# LifterV03.net
KiCad netlist of a schematic drawn in EAGLE
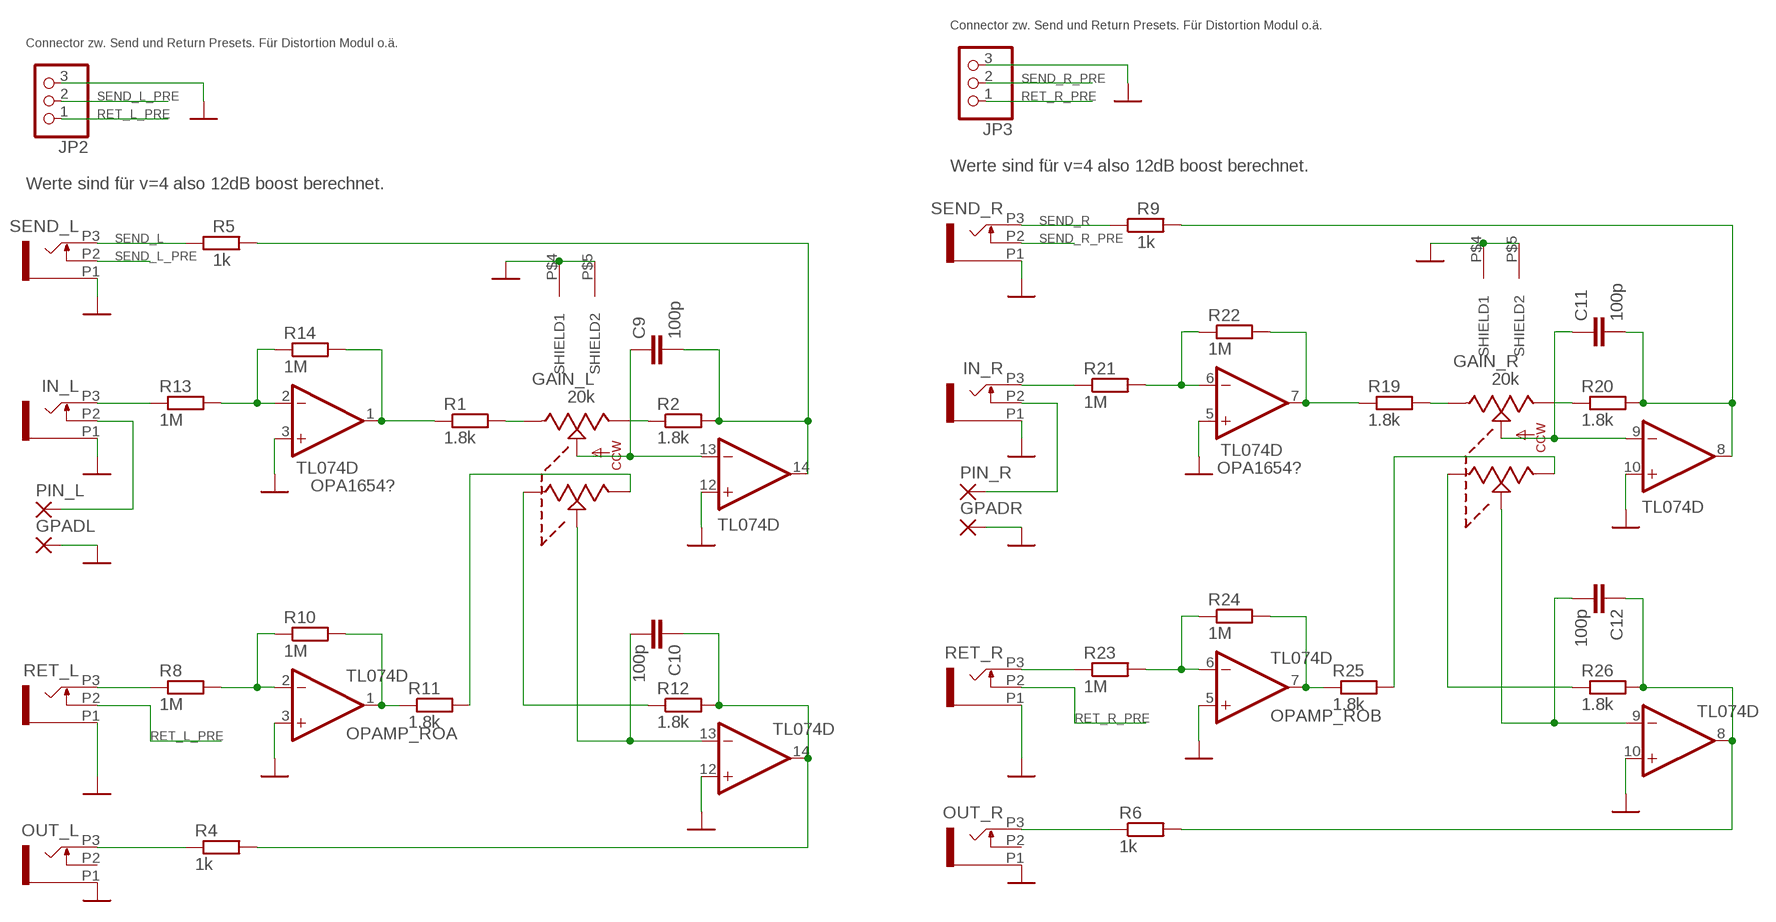
[diagram p0: schematic, sheet 1]
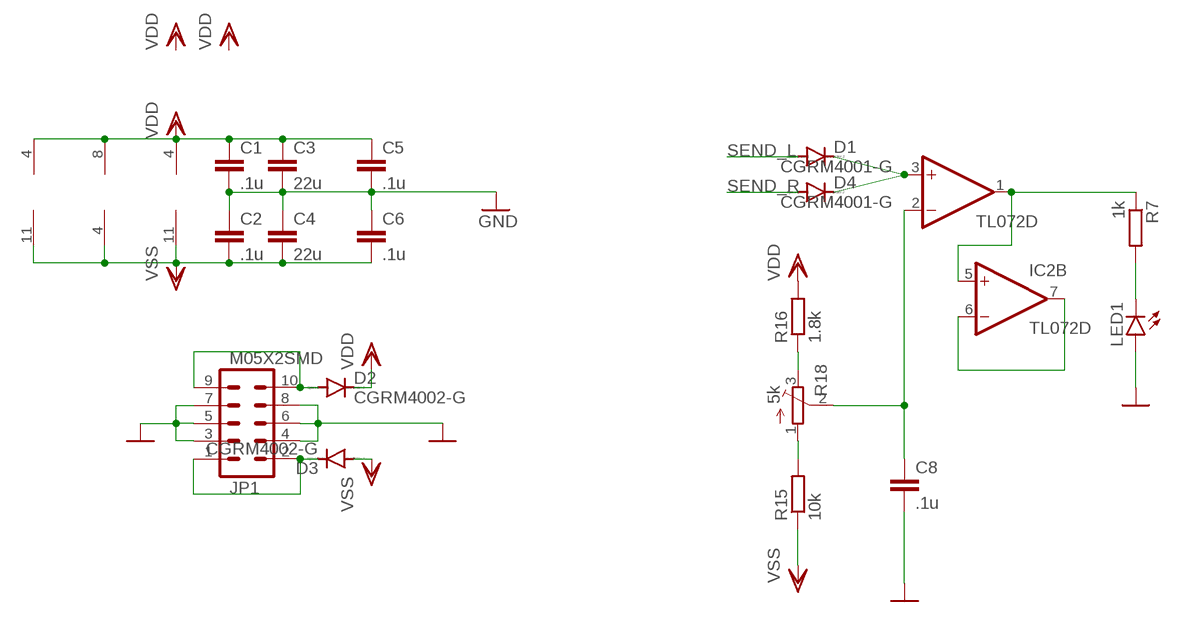
[diagram p1: schematic, sheet 2]

(export (version "E")
  (design (tool "Eeschema 10.0.6"))
  (components
    (comp (ref "C9")
      (value "100p")
      (footprint "eagle-import:C0603")
      (libsource (lib "eagle-import") (part "C-EUC0603"))
    )
    (comp (ref "C10")
      (value "100p")
      (footprint "eagle-import:C0603")
      (libsource (lib "eagle-import") (part "C-EUC0603"))
    )
    (comp (ref "C11")
      (value "100p")
      (footprint "eagle-import:C0603")
      (libsource (lib "eagle-import") (part "C-EUC0603"))
    )
    (comp (ref "C12")
      (value "100p")
      (footprint "eagle-import:C0603")
      (libsource (lib "eagle-import") (part "C-EUC0603"))
    )
    (comp (ref "GAIN_L")
      (value "20k")
      (footprint "eagle-import:TT_2TAP_VERTICAL")
      (libsource (lib "eagle-import") (part "POT_US_2X"))
    )
    (comp (ref "GAIN_R")
      (value "20k")
      (footprint "eagle-import:TT_2TAP_VERTICAL")
      (libsource (lib "eagle-import") (part "POT_US_2X"))
    )
    (comp (ref "GPADL")
      (value "3,17/1,3")
      (footprint "eagle-import:3,17_1,3")
      (libsource (lib "eagle-import") (part "3,17/1,3"))
    )
    (comp (ref "GPADR")
      (value "3,17/1,3")
      (footprint "eagle-import:3,17_1,3")
      (libsource (lib "eagle-import") (part "3,17/1,3"))
    )
    (comp (ref "IN_L")
      (value "PJ301_THONKICONN6")
      (footprint "eagle-import:WQP_PJ_301M6")
      (libsource (lib "eagle-import") (part "PJ301_THONKICONN6"))
    )
    (comp (ref "IN_R")
      (value "PJ301_THONKICONN6")
      (footprint "eagle-import:WQP_PJ_301M6")
      (libsource (lib "eagle-import") (part "PJ301_THONKICONN6"))
    )
    (comp (ref "JP2")
      (value "PINHD-1X3")
      (footprint "eagle-import:1X03")
      (libsource (lib "eagle-import") (part "PINHD-1X3"))
    )
    (comp (ref "JP3")
      (value "PINHD-1X3")
      (footprint "eagle-import:1X03")
      (libsource (lib "eagle-import") (part "PINHD-1X3"))
    )
    (comp (ref "OPAMP_IS")
      (value "TL074D")
      (footprint "eagle-import:SO14")
      (fields (field (name "SPICEPREFIX") "J"))
      (libsource (lib "eagle-import") (part "TL074D"))
    )
    (comp (ref "OPAMP_RO")
      (value "TL074D")
      (footprint "eagle-import:SO14")
      (fields (field (name "SPICEPREFIX") "J"))
      (libsource (lib "eagle-import") (part "TL074D"))
    )
    (comp (ref "OUT_L")
      (value "PJ301_THONKICONN6")
      (footprint "eagle-import:WQP_PJ_301M6")
      (libsource (lib "eagle-import") (part "PJ301_THONKICONN6"))
    )
    (comp (ref "OUT_R")
      (value "PJ301_THONKICONN6")
      (footprint "eagle-import:WQP_PJ_301M6")
      (libsource (lib "eagle-import") (part "PJ301_THONKICONN6"))
    )
    (comp (ref "PIN_L")
      (value "3,17/1,3")
      (footprint "eagle-import:3,17_1,3")
      (libsource (lib "eagle-import") (part "3,17/1,3"))
    )
    (comp (ref "PIN_R")
      (value "3,17/1,3")
      (footprint "eagle-import:3,17_1,3")
      (libsource (lib "eagle-import") (part "3,17/1,3"))
    )
    (comp (ref "R1")
      (value "1.8k")
      (footprint "eagle-import:R0603")
      (libsource (lib "eagle-import") (part "R-EU_R0603"))
    )
    (comp (ref "R2")
      (value "1.8k")
      (footprint "eagle-import:R0603")
      (libsource (lib "eagle-import") (part "R-EU_R0603"))
    )
    (comp (ref "R4")
      (value "1k")
      (footprint "eagle-import:R0603")
      (libsource (lib "eagle-import") (part "R-EU_R0603"))
    )
    (comp (ref "R5")
      (value "1k")
      (footprint "eagle-import:R0603")
      (libsource (lib "eagle-import") (part "R-EU_R0603"))
    )
    (comp (ref "R6")
      (value "1k")
      (footprint "eagle-import:R0603")
      (libsource (lib "eagle-import") (part "R-EU_R0603"))
    )
    (comp (ref "R8")
      (value "1M")
      (footprint "eagle-import:R0603")
      (libsource (lib "eagle-import") (part "R-EU_R0603"))
    )
    (comp (ref "R9")
      (value "1k")
      (footprint "eagle-import:R0603")
      (libsource (lib "eagle-import") (part "R-EU_R0603"))
    )
    (comp (ref "R10")
      (value "1M")
      (footprint "eagle-import:R0603")
      (libsource (lib "eagle-import") (part "R-EU_R0603"))
    )
    (comp (ref "R11")
      (value "1.8k")
      (footprint "eagle-import:R0603")
      (libsource (lib "eagle-import") (part "R-EU_R0603"))
    )
    (comp (ref "R12")
      (value "1.8k")
      (footprint "eagle-import:R0603")
      (libsource (lib "eagle-import") (part "R-EU_R0603"))
    )
    (comp (ref "R13")
      (value "1M")
      (footprint "eagle-import:R0603")
      (libsource (lib "eagle-import") (part "R-EU_R0603"))
    )
    (comp (ref "R14")
      (value "1M")
      (footprint "eagle-import:R0603")
      (libsource (lib "eagle-import") (part "R-EU_R0603"))
    )
    (comp (ref "R19")
      (value "1.8k")
      (footprint "eagle-import:R0603")
      (libsource (lib "eagle-import") (part "R-EU_R0603"))
    )
    (comp (ref "R20")
      (value "1.8k")
      (footprint "eagle-import:R0603")
      (libsource (lib "eagle-import") (part "R-EU_R0603"))
    )
    (comp (ref "R21")
      (value "1M")
      (footprint "eagle-import:R0603")
      (libsource (lib "eagle-import") (part "R-EU_R0603"))
    )
    (comp (ref "R22")
      (value "1M")
      (footprint "eagle-import:R0603")
      (libsource (lib "eagle-import") (part "R-EU_R0603"))
    )
    (comp (ref "R23")
      (value "1M")
      (footprint "eagle-import:R0603")
      (libsource (lib "eagle-import") (part "R-EU_R0603"))
    )
    (comp (ref "R24")
      (value "1M")
      (footprint "eagle-import:R0603")
      (libsource (lib "eagle-import") (part "R-EU_R0603"))
    )
    (comp (ref "R25")
      (value "1.8k")
      (footprint "eagle-import:R0603")
      (libsource (lib "eagle-import") (part "R-EU_R0603"))
    )
    (comp (ref "R26")
      (value "1.8k")
      (footprint "eagle-import:R0603")
      (libsource (lib "eagle-import") (part "R-EU_R0603"))
    )
    (comp (ref "RET_L")
      (value "PJ301_THONKICONN6")
      (footprint "eagle-import:WQP_PJ_301M6")
      (libsource (lib "eagle-import") (part "PJ301_THONKICONN6"))
    )
    (comp (ref "RET_R")
      (value "PJ301_THONKICONN6")
      (footprint "eagle-import:WQP_PJ_301M6")
      (libsource (lib "eagle-import") (part "PJ301_THONKICONN6"))
    )
    (comp (ref "SEND_L")
      (value "PJ301_THONKICONN6")
      (footprint "eagle-import:WQP_PJ_301M6")
      (libsource (lib "eagle-import") (part "PJ301_THONKICONN6"))
    )
    (comp (ref "SEND_R")
      (value "PJ301_THONKICONN6")
      (footprint "eagle-import:WQP_PJ_301M6")
      (libsource (lib "eagle-import") (part "PJ301_THONKICONN6"))
    )
    (comp (ref "C1")
      (value ".1u")
      (footprint "eagle-import:C0603")
      (libsource (lib "eagle-import") (part "C-EUC0603"))
    )
    (comp (ref "C2")
      (value ".1u")
      (footprint "eagle-import:C0603")
      (libsource (lib "eagle-import") (part "C-EUC0603"))
    )
    (comp (ref "C3")
      (value "22u")
      (footprint "eagle-import:C1210")
      (libsource (lib "eagle-import") (part "C-EUC1210"))
    )
    (comp (ref "C4")
      (value "22u")
      (footprint "eagle-import:C1210")
      (libsource (lib "eagle-import") (part "C-EUC1210"))
    )
    (comp (ref "C5")
      (value ".1u")
      (footprint "eagle-import:C0603")
      (libsource (lib "eagle-import") (part "C-EUC0603"))
    )
    (comp (ref "C6")
      (value ".1u")
      (footprint "eagle-import:C0603")
      (libsource (lib "eagle-import") (part "C-EUC0603"))
    )
    (comp (ref "C8")
      (value ".1u")
      (footprint "eagle-import:C0603")
      (libsource (lib "eagle-import") (part "C-EUC0603"))
    )
    (comp (ref "D1")
      (value "CGRM4001-G")
      (footprint "eagle-import:SOD-123_MINI-SMA")
      (libsource (lib "eagle-import") (part "CGRM400-G1"))
    )
    (comp (ref "D2")
      (value "CGRM4002-G")
      (footprint "eagle-import:SOD-123_MINI-SMA")
      (libsource (lib "eagle-import") (part "CGRM400-G2"))
    )
    (comp (ref "D3")
      (value "CGRM4002-G")
      (footprint "eagle-import:SOD-123_MINI-SMA")
      (libsource (lib "eagle-import") (part "CGRM400-G2"))
    )
    (comp (ref "D4")
      (value "CGRM4001-G")
      (footprint "eagle-import:SOD-123_MINI-SMA")
      (libsource (lib "eagle-import") (part "CGRM400-G1"))
    )
    (comp (ref "IC2")
      (value "TL072D")
      (footprint "eagle-import:SO08")
      (libsource (lib "eagle-import") (part "TL072D"))
    )
    (comp (ref "JP1")
      (value "M05X2SMD")
      (footprint "eagle-import:2X5-SMD")
      (libsource (lib "eagle-import") (part "M05X2SMD"))
    )
    (comp (ref "LED1")
      (value "LED3MM")
      (footprint "eagle-import:LED3MM")
      (libsource (lib "eagle-import") (part "LED3MM"))
    )
    (comp (ref "R7")
      (value "1k")
      (footprint "eagle-import:R0603")
      (libsource (lib "eagle-import") (part "R-EU_R0603"))
    )
    (comp (ref "R15")
      (value "10k")
      (footprint "eagle-import:R0603")
      (libsource (lib "eagle-import") (part "R-EU_R0603"))
    )
    (comp (ref "R16")
      (value "1.8k")
      (footprint "eagle-import:R0603")
      (libsource (lib "eagle-import") (part "R-EU_R0603"))
    )
    (comp (ref "R18")
      (value "5k")
      (footprint "eagle-import:3223G")
      (libsource (lib "eagle-import") (part "TRIM_EU-3223G"))
    )
  )
  (nets
    (net (code "1") (name "GND") (class "Default")
      (node (ref "C1") (pin "2") (pinfunction "2_2") (pintype "passive"))
      (node (ref "C2") (pin "1") (pinfunction "1_1") (pintype "passive"))
      (node (ref "C3") (pin "2") (pinfunction "2_2") (pintype "passive"))
      (node (ref "C4") (pin "1") (pinfunction "1_1") (pintype "passive"))
      (node (ref "C5") (pin "2") (pinfunction "2_2") (pintype "passive"))
      (node (ref "C6") (pin "1") (pinfunction "1_1") (pintype "passive"))
      (node (ref "C8") (pin "2") (pinfunction "2_2") (pintype "passive"))
      (node (ref "GAIN_L") (pin "P$4") (pinfunction "SHIELD1_P$4") (pintype "bidirectional"))
      (node (ref "GAIN_L") (pin "P$5") (pinfunction "SHIELD2_P$5") (pintype "bidirectional"))
      (node (ref "GAIN_R") (pin "P$4") (pinfunction "SHIELD1_P$4") (pintype "bidirectional"))
      (node (ref "GAIN_R") (pin "P$5") (pinfunction "SHIELD2_P$5") (pintype "bidirectional"))
      (node (ref "GPADL") (pin "1") (pinfunction "P_1") (pintype "passive"))
      (node (ref "GPADR") (pin "1") (pinfunction "P_1") (pintype "passive"))
      (node (ref "IN_L") (pin "P1") (pinfunction "1_P1") (pintype "passive"))
      (node (ref "IN_R") (pin "P1") (pinfunction "1_P1") (pintype "passive"))
      (node (ref "JP1") (pin "3") (pinfunction "3_3") (pintype "passive"))
      (node (ref "JP1") (pin "4") (pinfunction "4_4") (pintype "passive"))
      (node (ref "JP1") (pin "5") (pinfunction "5_5") (pintype "passive"))
      (node (ref "JP1") (pin "6") (pinfunction "6_6") (pintype "passive"))
      (node (ref "JP1") (pin "7") (pinfunction "7_7") (pintype "passive"))
      (node (ref "JP1") (pin "8") (pinfunction "8_8") (pintype "passive"))
      (node (ref "JP2") (pin "3") (pinfunction "3_3") (pintype "passive"))
      (node (ref "JP3") (pin "3") (pinfunction "3_3") (pintype "passive"))
      (node (ref "LED1") (pin "A") (pinfunction "A_A") (pintype "passive"))
      (node (ref "OPAMP_IS") (pin "10") (pinfunction "+IN_10") (pintype "input"))
      (node (ref "OPAMP_IS") (pin "12") (pinfunction "+IN_12") (pintype "input"))
      (node (ref "OPAMP_IS") (pin "3") (pinfunction "+IN_3") (pintype "input"))
      (node (ref "OPAMP_IS") (pin "5") (pinfunction "+IN_5") (pintype "input"))
      (node (ref "OPAMP_RO") (pin "10") (pinfunction "+IN_10") (pintype "input"))
      (node (ref "OPAMP_RO") (pin "12") (pinfunction "+IN_12") (pintype "input"))
      (node (ref "OPAMP_RO") (pin "3") (pinfunction "+IN_3") (pintype "input"))
      (node (ref "OPAMP_RO") (pin "5") (pinfunction "+IN_5") (pintype "input"))
      (node (ref "OUT_L") (pin "P1") (pinfunction "1_P1") (pintype "passive"))
      (node (ref "OUT_R") (pin "P1") (pinfunction "1_P1") (pintype "passive"))
      (node (ref "RET_L") (pin "P1") (pinfunction "1_P1") (pintype "passive"))
      (node (ref "RET_R") (pin "P1") (pinfunction "1_P1") (pintype "passive"))
      (node (ref "SEND_L") (pin "P1") (pinfunction "1_P1") (pintype "passive"))
      (node (ref "SEND_R") (pin "P1") (pinfunction "1_P1") (pintype "passive"))
    )
    (net (code "2") (name "Net-(D2-PadA)") (class "Default")
      (node (ref "D2") (pin "A") (pinfunction "A_A") (pintype "passive"))
      (node (ref "JP1") (pin "10") (pinfunction "10_10") (pintype "passive"))
      (node (ref "JP1") (pin "9") (pinfunction "9_9") (pintype "passive"))
    )
    (net (code "3") (name "Net-(D3-PadC)") (class "Default")
      (node (ref "D3") (pin "C") (pinfunction "C_C") (pintype "passive"))
      (node (ref "JP1") (pin "1") (pinfunction "1_1") (pintype "passive"))
      (node (ref "JP1") (pin "2") (pinfunction "2_2") (pintype "passive"))
    )
    (net (code "4") (name "Net-(GAIN_L-PadCCW)") (class "Default")
      (node (ref "GAIN_L") (pin "CCW") (pinfunction "CCW_CCW") (pintype "passive"))
      (node (ref "R2") (pin "1") (pinfunction "1_1") (pintype "passive"))
    )
    (net (code "5") (name "Net-(GAIN_L-PadCCW1)") (class "Default")
      (node (ref "GAIN_L") (pin "CCW1") (pinfunction "CCW1_CCW1") (pintype "passive"))
      (node (ref "R11") (pin "2") (pinfunction "2_2") (pintype "passive"))
    )
    (net (code "6") (name "Net-(GAIN_L-PadCW)") (class "Default")
      (node (ref "GAIN_L") (pin "CW") (pinfunction "CW_CW") (pintype "passive"))
      (node (ref "R1") (pin "2") (pinfunction "2_2") (pintype "passive"))
    )
    (net (code "7") (name "Net-(GAIN_L-PadCW1)") (class "Default")
      (node (ref "GAIN_L") (pin "CW1") (pinfunction "CW1_CW1") (pintype "passive"))
      (node (ref "R12") (pin "1") (pinfunction "1_1") (pintype "passive"))
    )
    (net (code "8") (name "Net-(GAIN_R-PadCCW)") (class "Default")
      (node (ref "GAIN_R") (pin "CCW") (pinfunction "CCW_CCW") (pintype "passive"))
      (node (ref "R20") (pin "1") (pinfunction "1_1") (pintype "passive"))
    )
    (net (code "9") (name "Net-(GAIN_R-PadCCW1)") (class "Default")
      (node (ref "GAIN_R") (pin "CCW1") (pinfunction "CCW1_CCW1") (pintype "passive"))
      (node (ref "R25") (pin "2") (pinfunction "2_2") (pintype "passive"))
    )
    (net (code "10") (name "Net-(GAIN_R-PadCW)") (class "Default")
      (node (ref "GAIN_R") (pin "CW") (pinfunction "CW_CW") (pintype "passive"))
      (node (ref "R19") (pin "2") (pinfunction "2_2") (pintype "passive"))
    )
    (net (code "11") (name "Net-(GAIN_R-PadCW1)") (class "Default")
      (node (ref "GAIN_R") (pin "CW1") (pinfunction "CW1_CW1") (pintype "passive"))
      (node (ref "R26") (pin "1") (pinfunction "1_1") (pintype "passive"))
    )
    (net (code "12") (name "Net-(IC2A-+IN)") (class "Default")
      (node (ref "D1") (pin "C") (pinfunction "C_C") (pintype "passive"))
      (node (ref "D4") (pin "C") (pinfunction "C_C") (pintype "passive"))
      (node (ref "IC2") (pin "3") (pinfunction "+IN_3") (pintype "input"))
    )
    (net (code "13") (name "Net-(IC2A--IN)") (class "Default")
      (node (ref "C8") (pin "1") (pinfunction "1_1") (pintype "passive"))
      (node (ref "IC2") (pin "2") (pinfunction "-IN_2") (pintype "input"))
      (node (ref "R18") (pin "2") (pinfunction "S_2") (pintype "passive"))
    )
    (net (code "14") (name "Net-(IC2A-OUT)") (class "Default")
      (node (ref "IC2") (pin "1") (pinfunction "OUT_1") (pintype "output"))
      (node (ref "IC2") (pin "5") (pinfunction "+IN_5") (pintype "input"))
      (node (ref "R7") (pin "1") (pinfunction "1_1") (pintype "passive"))
    )
    (net (code "15") (name "Net-(IC2B--IN)") (class "Default")
      (node (ref "IC2") (pin "6") (pinfunction "-IN_6") (pintype "input"))
      (node (ref "IC2") (pin "7") (pinfunction "OUT_7") (pintype "output"))
    )
    (net (code "16") (name "Net-(IN_L-2)") (class "Default")
      (node (ref "IN_L") (pin "P2") (pinfunction "2_P2") (pintype "passive"))
      (node (ref "PIN_L") (pin "1") (pinfunction "P_1") (pintype "passive"))
    )
    (net (code "17") (name "Net-(IN_L-3)") (class "Default")
      (node (ref "IN_L") (pin "P3") (pinfunction "3_P3") (pintype "passive"))
      (node (ref "R13") (pin "1") (pinfunction "1_1") (pintype "passive"))
    )
    (net (code "18") (name "Net-(IN_R-2)") (class "Default")
      (node (ref "IN_R") (pin "P2") (pinfunction "2_P2") (pintype "passive"))
      (node (ref "PIN_R") (pin "1") (pinfunction "P_1") (pintype "passive"))
    )
    (net (code "19") (name "Net-(IN_R-3)") (class "Default")
      (node (ref "IN_R") (pin "P3") (pinfunction "3_P3") (pintype "passive"))
      (node (ref "R21") (pin "1") (pinfunction "1_1") (pintype "passive"))
    )
    (net (code "20") (name "Net-(LED1-C)") (class "Default")
      (node (ref "LED1") (pin "K") (pinfunction "C_K") (pintype "passive"))
      (node (ref "R7") (pin "2") (pinfunction "2_2") (pintype "passive"))
    )
    (net (code "21") (name "Net-(OPAMP_ISA--IN)") (class "Default")
      (node (ref "OPAMP_IS") (pin "2") (pinfunction "-IN_2") (pintype "input"))
      (node (ref "R13") (pin "2") (pinfunction "2_2") (pintype "passive"))
      (node (ref "R14") (pin "1") (pinfunction "1_1") (pintype "passive"))
    )
    (net (code "22") (name "Net-(OPAMP_ISA-OUT)") (class "Default")
      (node (ref "OPAMP_IS") (pin "1") (pinfunction "OUT_1") (pintype "output"))
      (node (ref "R1") (pin "1") (pinfunction "1_1") (pintype "passive"))
      (node (ref "R14") (pin "2") (pinfunction "2_2") (pintype "passive"))
    )
    (net (code "23") (name "Net-(OPAMP_ISB--IN)") (class "Default")
      (node (ref "OPAMP_IS") (pin "6") (pinfunction "-IN_6") (pintype "input"))
      (node (ref "R21") (pin "2") (pinfunction "2_2") (pintype "passive"))
      (node (ref "R22") (pin "1") (pinfunction "1_1") (pintype "passive"))
    )
    (net (code "24") (name "Net-(OPAMP_ISB-OUT)") (class "Default")
      (node (ref "OPAMP_IS") (pin "7") (pinfunction "OUT_7") (pintype "output"))
      (node (ref "R19") (pin "1") (pinfunction "1_1") (pintype "passive"))
      (node (ref "R22") (pin "2") (pinfunction "2_2") (pintype "passive"))
    )
    (net (code "25") (name "Net-(OPAMP_ISC--IN)") (class "Default")
      (node (ref "C11") (pin "1") (pinfunction "1_1") (pintype "passive"))
      (node (ref "GAIN_R") (pin "CENTER") (pinfunction "CENTER_CENTER") (pintype "passive"))
      (node (ref "OPAMP_IS") (pin "9") (pinfunction "-IN_9") (pintype "input"))
    )
    (net (code "26") (name "Net-(OPAMP_ISC-OUT)") (class "Default")
      (node (ref "C11") (pin "2") (pinfunction "2_2") (pintype "passive"))
      (node (ref "OPAMP_IS") (pin "8") (pinfunction "OUT_8") (pintype "output"))
      (node (ref "R20") (pin "2") (pinfunction "2_2") (pintype "passive"))
      (node (ref "R9") (pin "2") (pinfunction "2_2") (pintype "passive"))
    )
    (net (code "27") (name "Net-(OPAMP_ISD--IN)") (class "Default")
      (node (ref "C9") (pin "1") (pinfunction "1_1") (pintype "passive"))
      (node (ref "GAIN_L") (pin "CENTER") (pinfunction "CENTER_CENTER") (pintype "passive"))
      (node (ref "OPAMP_IS") (pin "13") (pinfunction "-IN_13") (pintype "input"))
    )
    (net (code "28") (name "Net-(OPAMP_ISD-OUT)") (class "Default")
      (node (ref "C9") (pin "2") (pinfunction "2_2") (pintype "passive"))
      (node (ref "OPAMP_IS") (pin "14") (pinfunction "OUT_14") (pintype "output"))
      (node (ref "R2") (pin "2") (pinfunction "2_2") (pintype "passive"))
      (node (ref "R5") (pin "2") (pinfunction "2_2") (pintype "passive"))
    )
    (net (code "29") (name "Net-(OPAMP_ROA--IN)") (class "Default")
      (node (ref "OPAMP_RO") (pin "2") (pinfunction "-IN_2") (pintype "input"))
      (node (ref "R10") (pin "1") (pinfunction "1_1") (pintype "passive"))
      (node (ref "R8") (pin "2") (pinfunction "2_2") (pintype "passive"))
    )
    (net (code "30") (name "Net-(OPAMP_ROA-OUT)") (class "Default")
      (node (ref "OPAMP_RO") (pin "1") (pinfunction "OUT_1") (pintype "output"))
      (node (ref "R10") (pin "2") (pinfunction "2_2") (pintype "passive"))
      (node (ref "R11") (pin "1") (pinfunction "1_1") (pintype "passive"))
    )
    (net (code "31") (name "Net-(OPAMP_ROB--IN)") (class "Default")
      (node (ref "OPAMP_RO") (pin "6") (pinfunction "-IN_6") (pintype "input"))
      (node (ref "R23") (pin "2") (pinfunction "2_2") (pintype "passive"))
      (node (ref "R24") (pin "1") (pinfunction "1_1") (pintype "passive"))
    )
    (net (code "32") (name "Net-(OPAMP_ROB-OUT)") (class "Default")
      (node (ref "OPAMP_RO") (pin "7") (pinfunction "OUT_7") (pintype "output"))
      (node (ref "R24") (pin "2") (pinfunction "2_2") (pintype "passive"))
      (node (ref "R25") (pin "1") (pinfunction "1_1") (pintype "passive"))
    )
    (net (code "33") (name "Net-(OPAMP_ROC--IN)") (class "Default")
      (node (ref "C12") (pin "2") (pinfunction "2_2") (pintype "passive"))
      (node (ref "GAIN_R") (pin "CENTER1") (pinfunction "CENTER1_CENTER1") (pintype "passive"))
      (node (ref "OPAMP_RO") (pin "9") (pinfunction "-IN_9") (pintype "input"))
    )
    (net (code "34") (name "Net-(OPAMP_ROC-OUT)") (class "Default")
      (node (ref "C12") (pin "1") (pinfunction "1_1") (pintype "passive"))
      (node (ref "OPAMP_RO") (pin "8") (pinfunction "OUT_8") (pintype "output"))
      (node (ref "R26") (pin "2") (pinfunction "2_2") (pintype "passive"))
      (node (ref "R6") (pin "2") (pinfunction "2_2") (pintype "passive"))
    )
    (net (code "35") (name "Net-(OPAMP_ROD--IN)") (class "Default")
      (node (ref "C10") (pin "2") (pinfunction "2_2") (pintype "passive"))
      (node (ref "GAIN_L") (pin "CENTER1") (pinfunction "CENTER1_CENTER1") (pintype "passive"))
      (node (ref "OPAMP_RO") (pin "13") (pinfunction "-IN_13") (pintype "input"))
    )
    (net (code "36") (name "Net-(OPAMP_ROD-OUT)") (class "Default")
      (node (ref "C10") (pin "1") (pinfunction "1_1") (pintype "passive"))
      (node (ref "OPAMP_RO") (pin "14") (pinfunction "OUT_14") (pintype "output"))
      (node (ref "R12") (pin "2") (pinfunction "2_2") (pintype "passive"))
      (node (ref "R4") (pin "2") (pinfunction "2_2") (pintype "passive"))
    )
    (net (code "37") (name "Net-(OUT_L-3)") (class "Default")
      (node (ref "OUT_L") (pin "P3") (pinfunction "3_P3") (pintype "passive"))
      (node (ref "R4") (pin "1") (pinfunction "1_1") (pintype "passive"))
    )
    (net (code "38") (name "Net-(OUT_R-3)") (class "Default")
      (node (ref "OUT_R") (pin "P3") (pinfunction "3_P3") (pintype "passive"))
      (node (ref "R6") (pin "1") (pinfunction "1_1") (pintype "passive"))
    )
    (net (code "39") (name "Net-(R18-A)") (class "Default")
      (node (ref "R15") (pin "2") (pinfunction "2_2") (pintype "passive"))
      (node (ref "R18") (pin "1") (pinfunction "A_1") (pintype "passive"))
    )
    (net (code "40") (name "Net-(R18-E)") (class "Default")
      (node (ref "R16") (pin "1") (pinfunction "1_1") (pintype "passive"))
      (node (ref "R18") (pin "3") (pinfunction "E_3") (pintype "passive"))
    )
    (net (code "41") (name "Net-(RET_L-3)") (class "Default")
      (node (ref "R8") (pin "1") (pinfunction "1_1") (pintype "passive"))
      (node (ref "RET_L") (pin "P3") (pinfunction "3_P3") (pintype "passive"))
    )
    (net (code "42") (name "Net-(RET_R-3)") (class "Default")
      (node (ref "R23") (pin "1") (pinfunction "1_1") (pintype "passive"))
      (node (ref "RET_R") (pin "P3") (pinfunction "3_P3") (pintype "passive"))
    )
    (net (code "43") (name "RET_L_PRE") (class "Default")
      (node (ref "JP2") (pin "1") (pinfunction "1_1") (pintype "passive"))
      (node (ref "RET_L") (pin "P2") (pinfunction "2_P2") (pintype "passive"))
    )
    (net (code "44") (name "RET_R_PRE") (class "Default")
      (node (ref "JP3") (pin "1") (pinfunction "1_1") (pintype "passive"))
      (node (ref "RET_R") (pin "P2") (pinfunction "2_P2") (pintype "passive"))
    )
    (net (code "45") (name "SEND_L") (class "Default")
      (node (ref "D1") (pin "A") (pinfunction "A_A") (pintype "passive"))
      (node (ref "R5") (pin "1") (pinfunction "1_1") (pintype "passive"))
      (node (ref "SEND_L") (pin "P3") (pinfunction "3_P3") (pintype "passive"))
    )
    (net (code "46") (name "SEND_L_PRE") (class "Default")
      (node (ref "JP2") (pin "2") (pinfunction "2_2") (pintype "passive"))
      (node (ref "SEND_L") (pin "P2") (pinfunction "2_P2") (pintype "passive"))
    )
    (net (code "47") (name "SEND_R") (class "Default")
      (node (ref "D4") (pin "A") (pinfunction "A_A") (pintype "passive"))
      (node (ref "R9") (pin "1") (pinfunction "1_1") (pintype "passive"))
      (node (ref "SEND_R") (pin "P3") (pinfunction "3_P3") (pintype "passive"))
    )
    (net (code "48") (name "SEND_R_PRE") (class "Default")
      (node (ref "JP3") (pin "2") (pinfunction "2_2") (pintype "passive"))
      (node (ref "SEND_R") (pin "P2") (pinfunction "2_P2") (pintype "passive"))
    )
    (net (code "49") (name "VDD") (class "Default")
      (node (ref "C1") (pin "1") (pinfunction "1_1") (pintype "passive"))
      (node (ref "C3") (pin "1") (pinfunction "1_1") (pintype "passive"))
      (node (ref "C5") (pin "1") (pinfunction "1_1") (pintype "passive"))
      (node (ref "D2") (pin "C") (pinfunction "C_C") (pintype "passive"))
      (node (ref "IC2") (pin "8") (pinfunction "V+_8") (pintype "power_in"))
      (node (ref "OPAMP_IS") (pin "4") (pinfunction "V+_4") (pintype "power_in"))
      (node (ref "OPAMP_RO") (pin "4") (pinfunction "V+_4") (pintype "power_in"))
      (node (ref "R16") (pin "2") (pinfunction "2_2") (pintype "passive"))
    )
    (net (code "50") (name "VSS") (class "Default")
      (node (ref "C2") (pin "2") (pinfunction "2_2") (pintype "passive"))
      (node (ref "C4") (pin "2") (pinfunction "2_2") (pintype "passive"))
      (node (ref "C6") (pin "2") (pinfunction "2_2") (pintype "passive"))
      (node (ref "D3") (pin "A") (pinfunction "A_A") (pintype "passive"))
      (node (ref "IC2") (pin "4") (pinfunction "V-_4") (pintype "power_in"))
      (node (ref "OPAMP_IS") (pin "11") (pinfunction "V-_11") (pintype "power_in"))
      (node (ref "OPAMP_RO") (pin "11") (pinfunction "V-_11") (pintype "power_in"))
      (node (ref "R15") (pin "1") (pinfunction "1_1") (pintype "passive"))
    )
    (net (code "51") (name "unconnected-(OUT_L-2-PadP2)") (class "Default")
      (node (ref "OUT_L") (pin "P2") (pinfunction "2_P2") (pintype "passive"))
    )
    (net (code "52") (name "unconnected-(OUT_R-2-PadP2)") (class "Default")
      (node (ref "OUT_R") (pin "P2") (pinfunction "2_P2") (pintype "passive"))
    )
  )
)
